# AVR_KSPIO.net
KiCad netlist of a schematic drawn in EAGLE
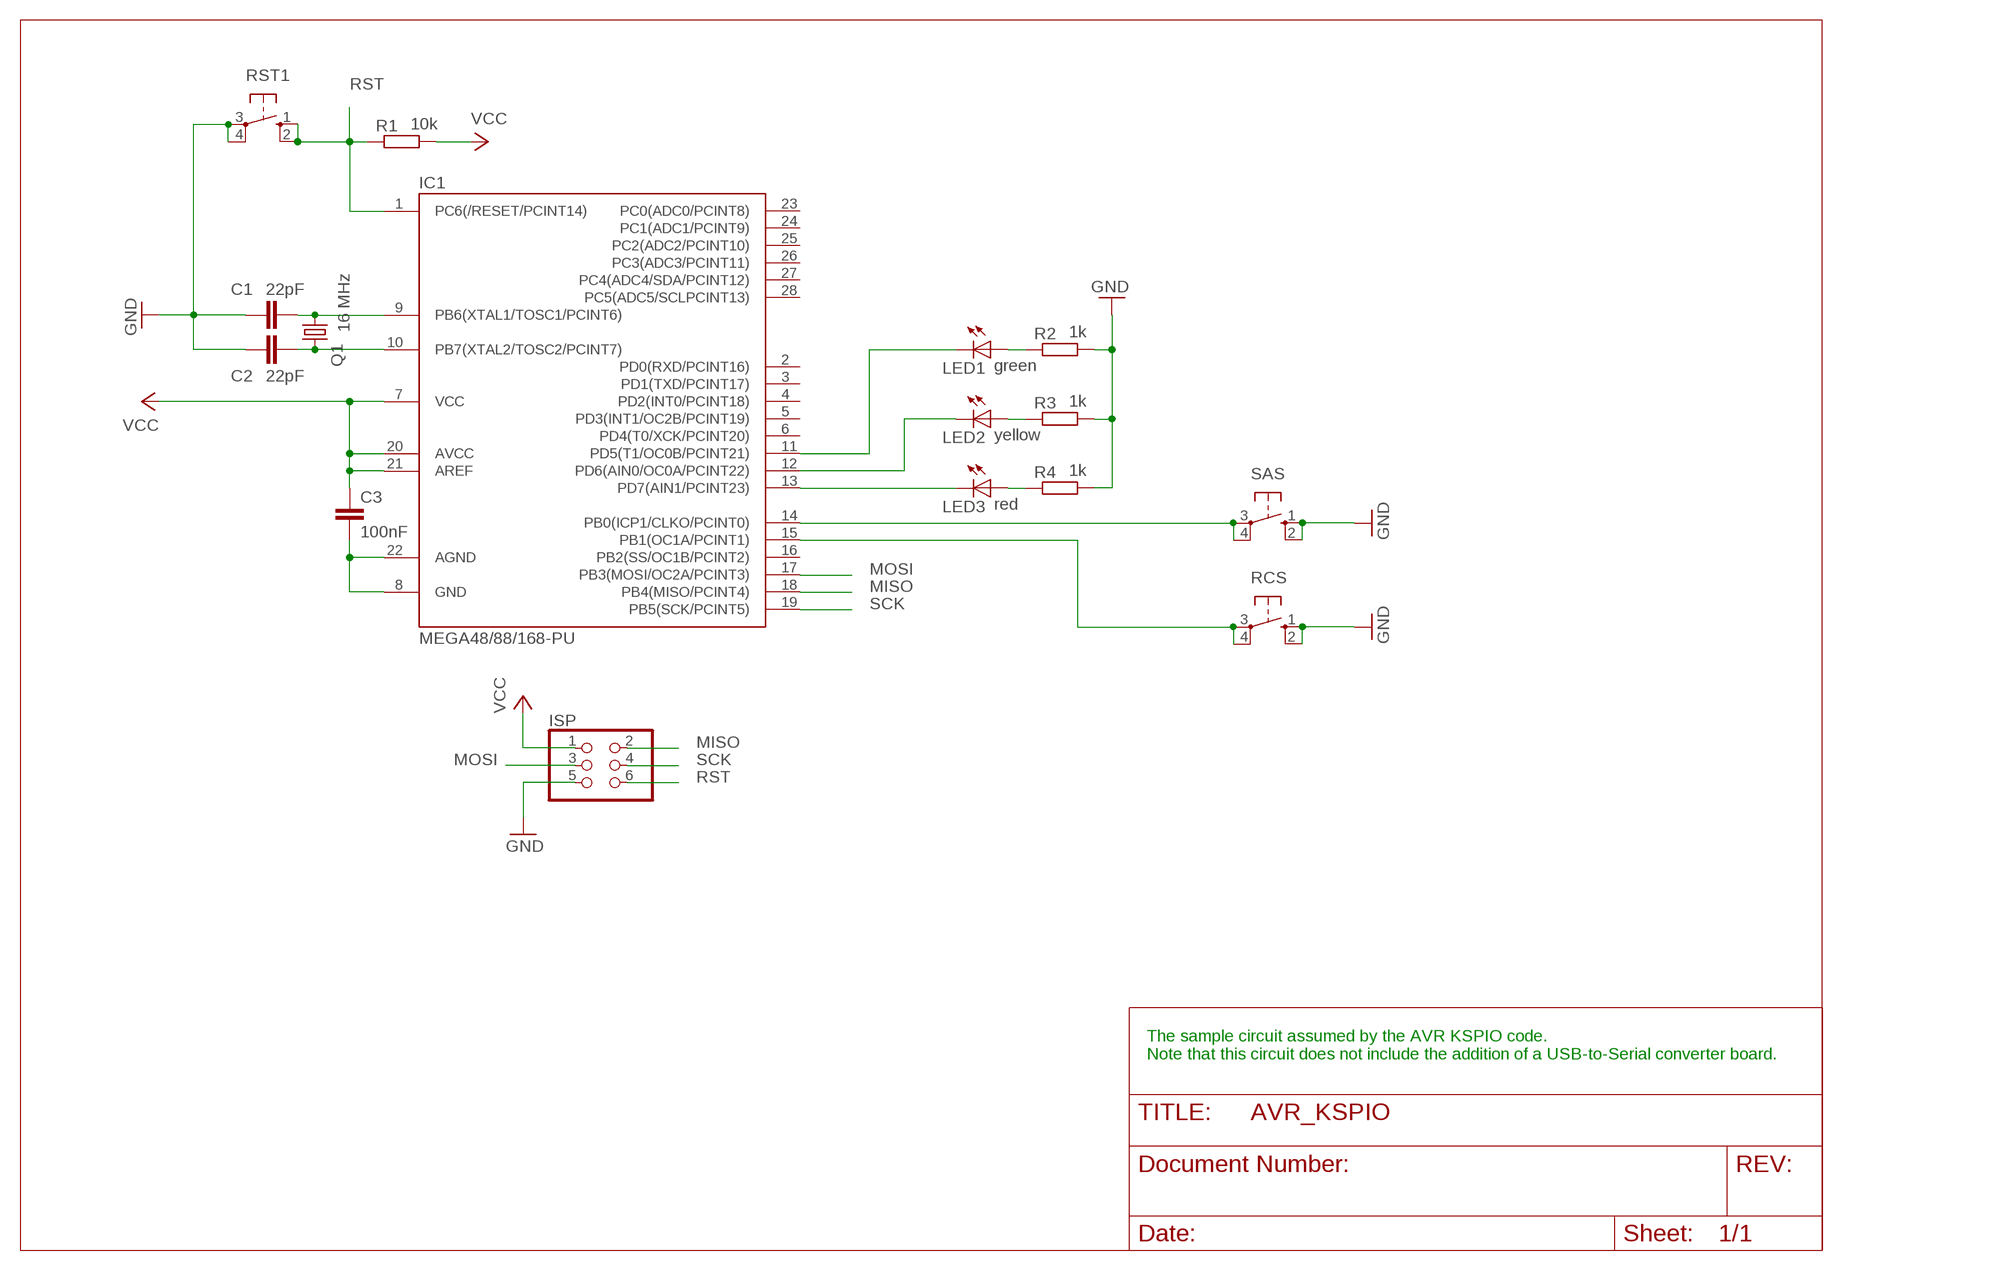
[diagram p0: schematic, sheet 1]

(export (version "E")
  (design (tool "Eeschema 10.0.6"))
  (components
    (comp (ref "C1")
      (value "22pF")
      (footprint "eagle-import:C025-024X044")
      (libsource (lib "eagle-import") (part "C-EU025-024X044"))
    )
    (comp (ref "C2")
      (value "22pF")
      (footprint "eagle-import:C025-024X044")
      (libsource (lib "eagle-import") (part "C-EU025-024X044"))
    )
    (comp (ref "C3")
      (value "100nF")
      (footprint "eagle-import:C025-024X044")
      (libsource (lib "eagle-import") (part "C-EU025-024X044"))
    )
    (comp (ref "IC1")
      (value "MEGA48/88/168-PU")
      (footprint "eagle-import:DIL28-3")
      (libsource (lib "eagle-import") (part "MEGA48/88/168-PU"))
    )
    (comp (ref "ISP")
      (value "PINHD-2X3")
      (footprint "eagle-import:2X03")
      (libsource (lib "eagle-import") (part "PINHD-2X3"))
    )
    (comp (ref "LED1")
      (value "green")
      (footprint "eagle-import:LED3MM")
      (libsource (lib "eagle-import") (part "LED3MM"))
    )
    (comp (ref "LED2")
      (value "yellow")
      (footprint "eagle-import:LED3MM")
      (libsource (lib "eagle-import") (part "LED3MM"))
    )
    (comp (ref "LED3")
      (value "red")
      (footprint "eagle-import:LED3MM")
      (libsource (lib "eagle-import") (part "LED3MM"))
    )
    (comp (ref "Q1")
      (value "16 MHz")
      (footprint "eagle-import:HC49_S")
      (libsource (lib "eagle-import") (part "CRYSTALHC49S"))
    )
    (comp (ref "R1")
      (value "10k")
      (footprint "eagle-import:0204_7")
      (libsource (lib "eagle-import") (part "R-EU_0204/7"))
    )
    (comp (ref "R2")
      (value "1k")
      (footprint "eagle-import:0204_7")
      (libsource (lib "eagle-import") (part "R-EU_0204/7"))
    )
    (comp (ref "R3")
      (value "1k")
      (footprint "eagle-import:0204_7")
      (libsource (lib "eagle-import") (part "R-EU_0204/7"))
    )
    (comp (ref "R4")
      (value "1k")
      (footprint "eagle-import:0204_7")
      (libsource (lib "eagle-import") (part "R-EU_0204/7"))
    )
    (comp (ref "RCS")
      (value "10-XX")
      (footprint "eagle-import:B3F-10XX")
      (fields (field (name "MPN") "B3F-1000"))
      (libsource (lib "eagle-import") (part "10-XX"))
    )
    (comp (ref "RST1")
      (value "10-XX")
      (footprint "eagle-import:B3F-10XX")
      (fields (field (name "MPN") "B3F-1000"))
      (libsource (lib "eagle-import") (part "10-XX"))
    )
    (comp (ref "SAS")
      (value "10-XX")
      (footprint "eagle-import:B3F-10XX")
      (fields (field (name "MPN") "B3F-1000"))
      (libsource (lib "eagle-import") (part "10-XX"))
    )
  )
  (nets
    (net (code "1") (name "/MISO") (class "Default")
      (node (ref "IC1") (pin "18") (pinfunction "PB4(MISO/PCINT4)_18") (pintype "bidirectional"))
      (node (ref "ISP") (pin "2") (pinfunction "2_2") (pintype "passive"))
    )
    (net (code "2") (name "/MOSI") (class "Default")
      (node (ref "IC1") (pin "17") (pinfunction "PB3(MOSI/OC2A/PCINT3)_17") (pintype "bidirectional"))
      (node (ref "ISP") (pin "3") (pinfunction "3_3") (pintype "passive"))
    )
    (net (code "3") (name "/RST") (class "Default")
      (node (ref "IC1") (pin "1") (pinfunction "PC6(/RESET/PCINT14)_1") (pintype "bidirectional"))
      (node (ref "ISP") (pin "6") (pinfunction "6_6") (pintype "passive"))
      (node (ref "R1") (pin "1") (pinfunction "1_1") (pintype "passive"))
      (node (ref "RST1") (pin "1") (pinfunction "S_1") (pintype "passive"))
      (node (ref "RST1") (pin "2") (pinfunction "S1_2") (pintype "passive"))
    )
    (net (code "4") (name "/SCK") (class "Default")
      (node (ref "IC1") (pin "19") (pinfunction "PB5(SCK/PCINT5)_19") (pintype "bidirectional"))
      (node (ref "ISP") (pin "4") (pinfunction "4_4") (pintype "passive"))
    )
    (net (code "5") (name "GND") (class "Default")
      (node (ref "C1") (pin "1") (pinfunction "1_1") (pintype "passive"))
      (node (ref "C2") (pin "1") (pinfunction "1_1") (pintype "passive"))
      (node (ref "ISP") (pin "5") (pinfunction "5_5") (pintype "passive"))
      (node (ref "R2") (pin "2") (pinfunction "2_2") (pintype "passive"))
      (node (ref "R3") (pin "2") (pinfunction "2_2") (pintype "passive"))
      (node (ref "R4") (pin "2") (pinfunction "2_2") (pintype "passive"))
      (node (ref "RCS") (pin "1") (pinfunction "S_1") (pintype "passive"))
      (node (ref "RCS") (pin "2") (pinfunction "S1_2") (pintype "passive"))
      (node (ref "RST1") (pin "3") (pinfunction "P_3") (pintype "passive"))
      (node (ref "RST1") (pin "4") (pinfunction "P1_4") (pintype "passive"))
      (node (ref "SAS") (pin "1") (pinfunction "S_1") (pintype "passive"))
      (node (ref "SAS") (pin "2") (pinfunction "S1_2") (pintype "passive"))
    )
    (net (code "6") (name "Net-(IC1-AGND)") (class "Default")
      (node (ref "C3") (pin "2") (pinfunction "2_2") (pintype "passive"))
      (node (ref "IC1") (pin "22") (pinfunction "AGND_22") (pintype "power_in"))
      (node (ref "IC1") (pin "8") (pinfunction "GND_8") (pintype "power_in"))
    )
    (net (code "7") (name "Net-(IC1-PB0(ICP1{slash}CLKO{slash}PCINT0))") (class "Default")
      (node (ref "IC1") (pin "14") (pinfunction "PB0(ICP1/CLKO/PCINT0)_14") (pintype "bidirectional"))
      (node (ref "SAS") (pin "3") (pinfunction "P_3") (pintype "passive"))
      (node (ref "SAS") (pin "4") (pinfunction "P1_4") (pintype "passive"))
    )
    (net (code "8") (name "Net-(IC1-PB1(OC1A{slash}PCINT1))") (class "Default")
      (node (ref "IC1") (pin "15") (pinfunction "PB1(OC1A/PCINT1)_15") (pintype "bidirectional"))
      (node (ref "RCS") (pin "3") (pinfunction "P_3") (pintype "passive"))
      (node (ref "RCS") (pin "4") (pinfunction "P1_4") (pintype "passive"))
    )
    (net (code "9") (name "Net-(IC1-PB6(XTAL1{slash}TOSC1{slash}PCINT6))") (class "Default")
      (node (ref "C1") (pin "2") (pinfunction "2_2") (pintype "passive"))
      (node (ref "IC1") (pin "9") (pinfunction "PB6(XTAL1/TOSC1/PCINT6)_9") (pintype "bidirectional"))
      (node (ref "Q1") (pin "2") (pinfunction "2_2") (pintype "passive"))
    )
    (net (code "10") (name "Net-(IC1-PB7(XTAL2{slash}TOSC2{slash}PCINT7))") (class "Default")
      (node (ref "C2") (pin "2") (pinfunction "2_2") (pintype "passive"))
      (node (ref "IC1") (pin "10") (pinfunction "PB7(XTAL2/TOSC2/PCINT7)_10") (pintype "bidirectional"))
      (node (ref "Q1") (pin "1") (pinfunction "1_1") (pintype "passive"))
    )
    (net (code "11") (name "Net-(IC1-PD5(T1{slash}OC0B{slash}PCINT21))") (class "Default")
      (node (ref "IC1") (pin "11") (pinfunction "PD5(T1/OC0B/PCINT21)_11") (pintype "bidirectional"))
      (node (ref "LED1") (pin "K") (pinfunction "C_K") (pintype "passive"))
    )
    (net (code "12") (name "Net-(IC1-PD6(AIN0{slash}OC0A{slash}PCINT22))") (class "Default")
      (node (ref "IC1") (pin "12") (pinfunction "PD6(AIN0/OC0A/PCINT22)_12") (pintype "bidirectional"))
      (node (ref "LED2") (pin "K") (pinfunction "C_K") (pintype "passive"))
    )
    (net (code "13") (name "Net-(IC1-PD7(AIN1{slash}PCINT23))") (class "Default")
      (node (ref "IC1") (pin "13") (pinfunction "PD7(AIN1/PCINT23)_13") (pintype "bidirectional"))
      (node (ref "LED3") (pin "K") (pinfunction "C_K") (pintype "passive"))
    )
    (net (code "14") (name "Net-(LED1-PadA)") (class "Default")
      (node (ref "LED1") (pin "A") (pinfunction "A_A") (pintype "passive"))
      (node (ref "R2") (pin "1") (pinfunction "1_1") (pintype "passive"))
    )
    (net (code "15") (name "Net-(LED2-PadA)") (class "Default")
      (node (ref "LED2") (pin "A") (pinfunction "A_A") (pintype "passive"))
      (node (ref "R3") (pin "1") (pinfunction "1_1") (pintype "passive"))
    )
    (net (code "16") (name "Net-(LED3-PadA)") (class "Default")
      (node (ref "LED3") (pin "A") (pinfunction "A_A") (pintype "passive"))
      (node (ref "R4") (pin "1") (pinfunction "1_1") (pintype "passive"))
    )
    (net (code "17") (name "VCC") (class "Default")
      (node (ref "C3") (pin "1") (pinfunction "1_1") (pintype "passive"))
      (node (ref "IC1") (pin "20") (pinfunction "AVCC_20") (pintype "passive"))
      (node (ref "IC1") (pin "21") (pinfunction "AREF_21") (pintype "passive"))
      (node (ref "IC1") (pin "7") (pinfunction "VCC_7") (pintype "power_in"))
      (node (ref "ISP") (pin "1") (pinfunction "1_1") (pintype "passive"))
      (node (ref "R1") (pin "2") (pinfunction "2_2") (pintype "passive"))
    )
    (net (code "18") (name "unconnected-(IC1-PB2(SS{slash}OC1B{slash}PCINT2)-Pad16)") (class "Default")
      (node (ref "IC1") (pin "16") (pinfunction "PB2(SS/OC1B/PCINT2)_16") (pintype "bidirectional"))
    )
    (net (code "19") (name "unconnected-(IC1-PC0(ADC0{slash}PCINT8)-Pad23)") (class "Default")
      (node (ref "IC1") (pin "23") (pinfunction "PC0(ADC0/PCINT8)_23") (pintype "bidirectional"))
    )
    (net (code "20") (name "unconnected-(IC1-PC1(ADC1{slash}PCINT9)-Pad24)") (class "Default")
      (node (ref "IC1") (pin "24") (pinfunction "PC1(ADC1/PCINT9)_24") (pintype "bidirectional"))
    )
    (net (code "21") (name "unconnected-(IC1-PC2(ADC2{slash}PCINT10)-Pad25)") (class "Default")
      (node (ref "IC1") (pin "25") (pinfunction "PC2(ADC2/PCINT10)_25") (pintype "bidirectional"))
    )
    (net (code "22") (name "unconnected-(IC1-PC3(ADC3{slash}PCINT11)-Pad26)") (class "Default")
      (node (ref "IC1") (pin "26") (pinfunction "PC3(ADC3/PCINT11)_26") (pintype "bidirectional"))
    )
    (net (code "23") (name "unconnected-(IC1-PC4(ADC4{slash}SDA{slash}PCINT12)-Pad27)") (class "Default")
      (node (ref "IC1") (pin "27") (pinfunction "PC4(ADC4/SDA/PCINT12)_27") (pintype "bidirectional"))
    )
    (net (code "24") (name "unconnected-(IC1-PC5(ADC5{slash}SCLPCINT13)-Pad28)") (class "Default")
      (node (ref "IC1") (pin "28") (pinfunction "PC5(ADC5/SCLPCINT13)_28") (pintype "bidirectional"))
    )
    (net (code "25") (name "unconnected-(IC1-PD0(RXD{slash}PCINT16)-Pad2)") (class "Default")
      (node (ref "IC1") (pin "2") (pinfunction "PD0(RXD/PCINT16)_2") (pintype "bidirectional"))
    )
    (net (code "26") (name "unconnected-(IC1-PD1(TXD{slash}PCINT17)-Pad3)") (class "Default")
      (node (ref "IC1") (pin "3") (pinfunction "PD1(TXD/PCINT17)_3") (pintype "bidirectional"))
    )
    (net (code "27") (name "unconnected-(IC1-PD2(INT0{slash}PCINT18)-Pad4)") (class "Default")
      (node (ref "IC1") (pin "4") (pinfunction "PD2(INT0/PCINT18)_4") (pintype "bidirectional"))
    )
    (net (code "28") (name "unconnected-(IC1-PD3(INT1{slash}OC2B{slash}PCINT19)-Pad5)") (class "Default")
      (node (ref "IC1") (pin "5") (pinfunction "PD3(INT1/OC2B/PCINT19)_5") (pintype "bidirectional"))
    )
    (net (code "29") (name "unconnected-(IC1-PD4(T0{slash}XCK{slash}PCINT20)-Pad6)") (class "Default")
      (node (ref "IC1") (pin "6") (pinfunction "PD4(T0/XCK/PCINT20)_6") (pintype "bidirectional"))
    )
  )
)
